# MCU.net
KiCad netlist of a schematic drawn in Altium Designer
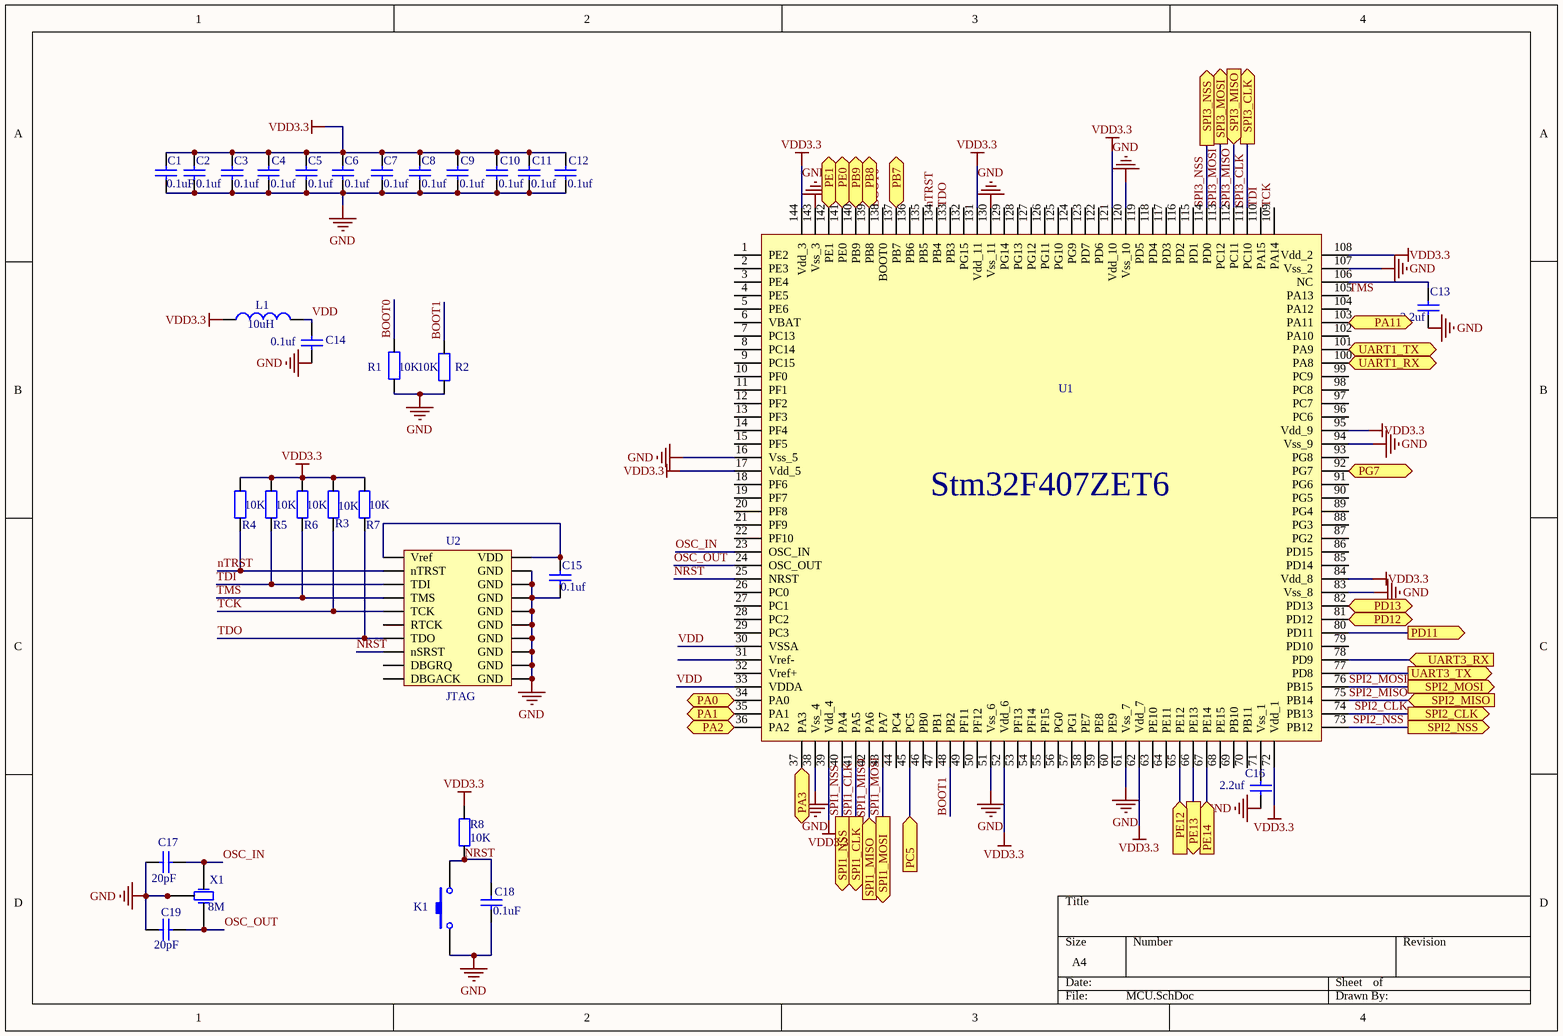
[diagram p0: MCU.SchDoc]

(export (version "E")
  (design (tool "Eeschema 10.0.6"))
  (components
    (comp (ref "C1")
      (value "0.1uF")
      (footprint "0603")
      (fields (field (name "Comment") "Capacitor-0805"))
      (libsource (lib "集成库—大岐") (part "Capacitor-0805"))
    )
    (comp (ref "C2")
      (value "0.1uf")
      (footprint "0603")
      (fields (field (name "Comment") "Capacitor-0805"))
      (libsource (lib "集成库—大岐") (part "Capacitor-0805"))
    )
    (comp (ref "C3")
      (value "0.1uf")
      (footprint "0603")
      (fields (field (name "Comment") "Capacitor-0805"))
      (libsource (lib "集成库—大岐") (part "Capacitor-0805"))
    )
    (comp (ref "C4")
      (value "0.1uf")
      (footprint "0603")
      (fields (field (name "Comment") "Capacitor-0805"))
      (libsource (lib "集成库—大岐") (part "Capacitor-0805"))
    )
    (comp (ref "C5")
      (value "0.1uf")
      (footprint "0603")
      (fields (field (name "Comment") "Capacitor-0805"))
      (libsource (lib "集成库—大岐") (part "Capacitor-0805"))
    )
    (comp (ref "C6")
      (value "0.1uf")
      (footprint "0603")
      (fields (field (name "Comment") "Capacitor-0805"))
      (libsource (lib "集成库—大岐") (part "Capacitor-0805"))
    )
    (comp (ref "C7")
      (value "0.1uf")
      (footprint "0603")
      (fields (field (name "Comment") "Capacitor-0805"))
      (libsource (lib "集成库—大岐") (part "Capacitor-0805"))
    )
    (comp (ref "C8")
      (value "0.1uf")
      (footprint "0603")
      (fields (field (name "Comment") "Capacitor-0805"))
      (libsource (lib "集成库—大岐") (part "Capacitor-0805"))
    )
    (comp (ref "C9")
      (value "0.1uf")
      (footprint "0603")
      (fields (field (name "Comment") "Capacitor-0805"))
      (libsource (lib "集成库—大岐") (part "Capacitor-0805"))
    )
    (comp (ref "C10")
      (value "0.1uf")
      (footprint "0603")
      (fields (field (name "Comment") "Capacitor-0805"))
      (libsource (lib "集成库—大岐") (part "Capacitor-0805"))
    )
    (comp (ref "C11")
      (value "0.1uf")
      (footprint "0603")
      (fields (field (name "Comment") "Capacitor-0805"))
      (libsource (lib "集成库—大岐") (part "Capacitor-0805"))
    )
    (comp (ref "C12")
      (value "0.1uf")
      (footprint "0603")
      (fields (field (name "Comment") "Capacitor-0805"))
      (libsource (lib "集成库—大岐") (part "Capacitor-0805"))
    )
    (comp (ref "C13")
      (value "2.2uf")
      (footprint "0603")
      (fields (field (name "Comment") "Capacitor-0603"))
      (libsource (lib "原理图库") (part "Capacitor-0603"))
    )
    (comp (ref "C14")
      (value "0.1uf")
      (footprint "0603")
      (fields (field (name "Comment") "Capacitor-0805"))
      (libsource (lib "集成库—大岐") (part "Capacitor-0805"))
    )
    (comp (ref "C15")
      (value "0.1uf")
      (footprint "0603")
      (fields (field (name "Comment") "Capacitor-0805"))
      (libsource (lib "集成库—大岐") (part "Capacitor-0805"))
    )
    (comp (ref "C16")
      (value "2.2uf")
      (footprint "0603")
      (fields (field (name "Comment") "Capacitor-0603"))
      (libsource (lib "原理图库") (part "Capacitor-0603"))
    )
    (comp (ref "C17")
      (value "20pF")
      (footprint "0603")
      (fields (field (name "Comment") "Capacitor-0805"))
      (libsource (lib "原理图库") (part "Capacitor-0805"))
    )
    (comp (ref "C18")
      (value "0.1uF")
      (footprint "0603")
      (fields (field (name "Comment") "Capacitor-0805"))
      (libsource (lib "原理图库") (part "Capacitor-0805"))
    )
    (comp (ref "C19")
      (value "20pF")
      (footprint "0603")
      (fields (field (name "Comment") "Capacitor-0805"))
      (libsource (lib "原理图库") (part "Capacitor-0805"))
    )
    (comp (ref "K1") (value "按键") (footprint "贴片按键") (libsource (lib "原理图库") (part "按键")))
    (comp (ref "L1")
      (value "10uH")
      (footprint "0805")
      (fields (field (name "Comment") "Inductor"))
      (libsource (lib "集成库—大岐") (part "Inductor"))
    )
    (comp (ref "R1")
      (value "10K")
      (footprint "0603")
      (fields (field (name "Comment") "Resistor-0805"))
      (libsource (lib "集成库—大岐") (part "Resistor-0805"))
    )
    (comp (ref "R2")
      (value "10K")
      (footprint "0603")
      (fields (field (name "Comment") "Resistor-0805"))
      (libsource (lib "集成库—大岐") (part "Resistor-0805"))
    )
    (comp (ref "R3")
      (value "10K")
      (footprint "0603")
      (fields (field (name "Comment") "Resistor-0805"))
      (libsource (lib "原理图库") (part "Resistor-0805"))
    )
    (comp (ref "R4")
      (value "10K")
      (footprint "0603")
      (fields (field (name "Comment") "Resistor-0805"))
      (libsource (lib "原理图库") (part "Resistor-0805"))
    )
    (comp (ref "R5")
      (value "10K")
      (footprint "0603")
      (fields (field (name "Comment") "Resistor-0805"))
      (libsource (lib "原理图库") (part "Resistor-0805"))
    )
    (comp (ref "R6")
      (value "10K")
      (footprint "0603")
      (fields (field (name "Comment") "Resistor-0805"))
      (libsource (lib "原理图库") (part "Resistor-0805"))
    )
    (comp (ref "R7")
      (value "10K")
      (footprint "0603")
      (fields (field (name "Comment") "Resistor-0805"))
      (libsource (lib "原理图库") (part "Resistor-0805"))
    )
    (comp (ref "R8")
      (value "10K")
      (footprint "0603")
      (fields (field (name "Comment") "Resistor-0805"))
      (libsource (lib "原理图库") (part "Resistor-0805"))
    )
    (comp (ref "U1")
      (value "STM32F407ZET6")
      (footprint "Stm32f407ZET6 - duplicate")
      (libsource (lib "原理图库") (part "STM32F407ZET6"))
    )
    (comp (ref "U2") (value "JTAG") (footprint "JTAG-20") (libsource (lib "原理图库") (part "JTAG")))
    (comp (ref "X1")
      (value "8M")
      (footprint "3225无源晶振")
      (fields (field (name "Comment") "3225无源晶振"))
      (libsource (lib "原理图库") (part "3225无源晶振"))
    )
  )
  (nets
    (net (code "1") (name "/BOOT0") (class "Default")
      (node (ref "R1") (pin "2") (pinfunction "2_2") (pintype "passive"))
      (node (ref "U1") (pin "138") (pinfunction "BOOT0_138") (pintype "passive"))
    )
    (net (code "2") (name "/BOOT1") (class "Default")
      (node (ref "R2") (pin "2") (pinfunction "2_2") (pintype "passive"))
      (node (ref "U1") (pin "48") (pinfunction "PB2_48") (pintype "passive"))
    )
    (net (code "3") (name "/NRST") (class "Default")
      (node (ref "C18") (pin "2") (pinfunction "2_2") (pintype "passive"))
      (node (ref "K1") (pin "2") (pinfunction "2_2") (pintype "passive"))
      (node (ref "R8") (pin "1") (pinfunction "1_1") (pintype "passive"))
      (node (ref "U1") (pin "25") (pinfunction "NRST_25") (pintype "passive"))
      (node (ref "U2") (pin "15") (pinfunction "nSRST_15") (pintype "passive"))
    )
    (net (code "4") (name "/OSC_IN") (class "Default")
      (node (ref "C17") (pin "2") (pinfunction "2_2") (pintype "passive"))
      (node (ref "U1") (pin "23") (pinfunction "OSC_IN_23") (pintype "passive"))
      (node (ref "X1") (pin "1") (pinfunction "OSC1_1") (pintype "passive"))
    )
    (net (code "5") (name "/OSC_OUT") (class "Default")
      (node (ref "C19") (pin "2") (pinfunction "2_2") (pintype "passive"))
      (node (ref "U1") (pin "24") (pinfunction "OSC_OUT_24") (pintype "passive"))
      (node (ref "X1") (pin "3") (pinfunction "OSC2_3") (pintype "passive"))
    )
    (net (code "6") (name "/PA0") (class "Default")
      (node (ref "U1") (pin "34") (pinfunction "PA0_34") (pintype "passive"))
    )
    (net (code "7") (name "/PA1") (class "Default")
      (node (ref "U1") (pin "35") (pinfunction "PA1_35") (pintype "passive"))
    )
    (net (code "8") (name "/PA2") (class "Default")
      (node (ref "U1") (pin "36") (pinfunction "PA2_36") (pintype "passive"))
    )
    (net (code "9") (name "/PA3") (class "Default")
      (node (ref "U1") (pin "37") (pinfunction "PA3_37") (pintype "passive"))
    )
    (net (code "10") (name "/PA11") (class "Default")
      (node (ref "U1") (pin "103") (pinfunction "PA11_103") (pintype "passive"))
    )
    (net (code "11") (name "/PB7") (class "Default")
      (node (ref "U1") (pin "137") (pinfunction "PB7_137") (pintype "passive"))
    )
    (net (code "12") (name "/PB8") (class "Default")
      (node (ref "U1") (pin "139") (pinfunction "PB8_139") (pintype "passive"))
    )
    (net (code "13") (name "/PB9") (class "Default")
      (node (ref "U1") (pin "140") (pinfunction "PB9_140") (pintype "passive"))
    )
    (net (code "14") (name "/PC5") (class "Default")
      (node (ref "U1") (pin "45") (pinfunction "PC5_45") (pintype "passive"))
    )
    (net (code "15") (name "/PD11") (class "Default")
      (node (ref "U1") (pin "80") (pinfunction "PD11_80") (pintype "passive"))
    )
    (net (code "16") (name "/PD12") (class "Default")
      (node (ref "U1") (pin "81") (pinfunction "PD12_81") (pintype "passive"))
    )
    (net (code "17") (name "/PD13") (class "Default")
      (node (ref "U1") (pin "82") (pinfunction "PD13_82") (pintype "passive"))
    )
    (net (code "18") (name "/PE0") (class "Default")
      (node (ref "U1") (pin "141") (pinfunction "PE0_141") (pintype "passive"))
    )
    (net (code "19") (name "/PE1") (class "Default")
      (node (ref "U1") (pin "142") (pinfunction "PE1_142") (pintype "passive"))
    )
    (net (code "20") (name "/PE12") (class "Default")
      (node (ref "U1") (pin "65") (pinfunction "PE12_65") (pintype "passive"))
    )
    (net (code "21") (name "/PE13") (class "Default")
      (node (ref "U1") (pin "66") (pinfunction "PE13_66") (pintype "passive"))
    )
    (net (code "22") (name "/PE14") (class "Default")
      (node (ref "U1") (pin "67") (pinfunction "PE14_67") (pintype "passive"))
    )
    (net (code "23") (name "/PG7") (class "Default")
      (node (ref "U1") (pin "92") (pinfunction "PG7_92") (pintype "passive"))
    )
    (net (code "24") (name "/SPI1_CLK") (class "Default")
      (node (ref "U1") (pin "41") (pinfunction "PA5_41") (pintype "passive"))
    )
    (net (code "25") (name "/SPI1_MISO") (class "Default")
      (node (ref "U1") (pin "42") (pinfunction "PA6_42") (pintype "passive"))
    )
    (net (code "26") (name "/SPI1_MOSI") (class "Default")
      (node (ref "U1") (pin "43") (pinfunction "PA7_43") (pintype "passive"))
    )
    (net (code "27") (name "/SPI1_NSS") (class "Default")
      (node (ref "U1") (pin "40") (pinfunction "PA4_40") (pintype "passive"))
    )
    (net (code "28") (name "/SPI2_CLK") (class "Default")
      (node (ref "U1") (pin "74") (pinfunction "PB13_74") (pintype "passive"))
    )
    (net (code "29") (name "/SPI2_MISO") (class "Default")
      (node (ref "U1") (pin "75") (pinfunction "PB14_75") (pintype "passive"))
    )
    (net (code "30") (name "/SPI2_MOSI") (class "Default")
      (node (ref "U1") (pin "76") (pinfunction "PB15_76") (pintype "passive"))
    )
    (net (code "31") (name "/SPI2_NSS") (class "Default")
      (node (ref "U1") (pin "73") (pinfunction "PB12_73") (pintype "passive"))
    )
    (net (code "32") (name "/SPI3_CLK") (class "Default")
      (node (ref "U1") (pin "111") (pinfunction "PC10_111") (pintype "passive"))
    )
    (net (code "33") (name "/SPI3_MISO") (class "Default")
      (node (ref "U1") (pin "112") (pinfunction "PC11_112") (pintype "passive"))
    )
    (net (code "34") (name "/SPI3_MOSI") (class "Default")
      (node (ref "U1") (pin "113") (pinfunction "PC12_113") (pintype "passive"))
    )
    (net (code "35") (name "/SPI3_NSS") (class "Default")
      (node (ref "U1") (pin "114") (pinfunction "PD0_114") (pintype "passive"))
    )
    (net (code "36") (name "/TCK") (class "Default")
      (node (ref "R3") (pin "1") (pinfunction "1_1") (pintype "passive"))
      (node (ref "U1") (pin "109") (pinfunction "PA14_109") (pintype "passive"))
      (node (ref "U2") (pin "9") (pinfunction "TCK_9") (pintype "passive"))
    )
    (net (code "37") (name "/TDI") (class "Default")
      (node (ref "R5") (pin "1") (pinfunction "1_1") (pintype "passive"))
      (node (ref "U1") (pin "110") (pinfunction "PA15_110") (pintype "passive"))
      (node (ref "U2") (pin "5") (pinfunction "TDI_5") (pintype "passive"))
    )
    (net (code "38") (name "/TDO") (class "Default")
      (node (ref "R7") (pin "1") (pinfunction "1_1") (pintype "passive"))
      (node (ref "U1") (pin "133") (pinfunction "PB3_133") (pintype "passive"))
      (node (ref "U2") (pin "13") (pinfunction "TDO_13") (pintype "passive"))
    )
    (net (code "39") (name "/TMS") (class "Default")
      (node (ref "R6") (pin "1") (pinfunction "1_1") (pintype "passive"))
      (node (ref "U1") (pin "105") (pinfunction "PA13_105") (pintype "passive"))
      (node (ref "U2") (pin "7") (pinfunction "TMS_7") (pintype "passive"))
    )
    (net (code "40") (name "/UART1_RX") (class "Default")
      (node (ref "U1") (pin "100") (pinfunction "PA8_100") (pintype "passive"))
    )
    (net (code "41") (name "/UART1_TX") (class "Default")
      (node (ref "U1") (pin "101") (pinfunction "PA9_101") (pintype "passive"))
    )
    (net (code "42") (name "/UART3_RX") (class "Default")
      (node (ref "U1") (pin "78") (pinfunction "PD9_78") (pintype "passive"))
    )
    (net (code "43") (name "/UART3_TX") (class "Default")
      (node (ref "U1") (pin "77") (pinfunction "PD8_77") (pintype "passive"))
    )
    (net (code "44") (name "/VDD") (class "Default")
      (node (ref "C14") (pin "2") (pinfunction "2_2") (pintype "passive"))
      (node (ref "L1") (pin "2") (pinfunction "2_2") (pintype "passive"))
      (node (ref "U1") (pin "30") (pinfunction "VSSA_30") (pintype "passive"))
      (node (ref "U1") (pin "33") (pinfunction "VDDA_33") (pintype "passive"))
    )
    (net (code "45") (name "/nTRST") (class "Default")
      (node (ref "R4") (pin "1") (pinfunction "1_1") (pintype "passive"))
      (node (ref "U1") (pin "134") (pinfunction "PB4_134") (pintype "passive"))
      (node (ref "U2") (pin "3") (pinfunction "nTRST_3") (pintype "passive"))
    )
    (net (code "46") (name "GND") (class "Default")
      (node (ref "C1") (pin "1") (pinfunction "1_1") (pintype "passive"))
      (node (ref "C10") (pin "1") (pinfunction "1_1") (pintype "passive"))
      (node (ref "C11") (pin "1") (pinfunction "1_1") (pintype "passive"))
      (node (ref "C12") (pin "1") (pinfunction "1_1") (pintype "passive"))
      (node (ref "C13") (pin "1") (pinfunction "1_1") (pintype "passive"))
      (node (ref "C14") (pin "1") (pinfunction "1_1") (pintype "passive"))
      (node (ref "C15") (pin "1") (pinfunction "1_1") (pintype "passive"))
      (node (ref "C16") (pin "1") (pinfunction "1_1") (pintype "passive"))
      (node (ref "C17") (pin "1") (pinfunction "1_1") (pintype "passive"))
      (node (ref "C18") (pin "1") (pinfunction "1_1") (pintype "passive"))
      (node (ref "C19") (pin "1") (pinfunction "1_1") (pintype "passive"))
      (node (ref "C2") (pin "1") (pinfunction "1_1") (pintype "passive"))
      (node (ref "C3") (pin "1") (pinfunction "1_1") (pintype "passive"))
      (node (ref "C4") (pin "1") (pinfunction "1_1") (pintype "passive"))
      (node (ref "C5") (pin "1") (pinfunction "1_1") (pintype "passive"))
      (node (ref "C6") (pin "1") (pinfunction "1_1") (pintype "passive"))
      (node (ref "C7") (pin "1") (pinfunction "1_1") (pintype "passive"))
      (node (ref "C8") (pin "1") (pinfunction "1_1") (pintype "passive"))
      (node (ref "C9") (pin "1") (pinfunction "1_1") (pintype "passive"))
      (node (ref "K1") (pin "1") (pinfunction "1_1") (pintype "passive"))
      (node (ref "R1") (pin "1") (pinfunction "1_1") (pintype "passive"))
      (node (ref "R2") (pin "1") (pinfunction "1_1") (pintype "passive"))
      (node (ref "U1") (pin "107") (pinfunction "Vss_2_107") (pintype "passive"))
      (node (ref "U1") (pin "120") (pinfunction "Vss_10_120") (pintype "passive"))
      (node (ref "U1") (pin "130") (pinfunction "Vss_11_130") (pintype "passive"))
      (node (ref "U1") (pin "143") (pinfunction "Vss_3_143") (pintype "passive"))
      (node (ref "U1") (pin "16") (pinfunction "Vss_5_16") (pintype "passive"))
      (node (ref "U1") (pin "38") (pinfunction "Vss_4_38") (pintype "passive"))
      (node (ref "U1") (pin "51") (pinfunction "Vss_6_51") (pintype "passive"))
      (node (ref "U1") (pin "61") (pinfunction "Vss_7_61") (pintype "passive"))
      (node (ref "U1") (pin "83") (pinfunction "Vss_8_83") (pintype "passive"))
      (node (ref "U1") (pin "94") (pinfunction "Vss_9_94") (pintype "passive"))
      (node (ref "U2") (pin "10") (pinfunction "GND_10") (pintype "passive"))
      (node (ref "U2") (pin "12") (pinfunction "GND_12") (pintype "passive"))
      (node (ref "U2") (pin "14") (pinfunction "GND_14") (pintype "passive"))
      (node (ref "U2") (pin "16") (pinfunction "GND_16") (pintype "passive"))
      (node (ref "U2") (pin "18") (pinfunction "GND_18") (pintype "passive"))
      (node (ref "U2") (pin "20") (pinfunction "GND_20") (pintype "passive"))
      (node (ref "U2") (pin "4") (pinfunction "GND_4") (pintype "passive"))
      (node (ref "U2") (pin "6") (pinfunction "GND_6") (pintype "passive"))
      (node (ref "U2") (pin "8") (pinfunction "GND_8") (pintype "passive"))
      (node (ref "X1") (pin "2") (pinfunction "GND_2") (pintype "passive"))
      (node (ref "X1") (pin "4") (pinfunction "GND_4") (pintype "passive"))
    )
    (net (code "47") (name "Net-(U1-NC)") (class "Default")
      (node (ref "C13") (pin "2") (pinfunction "2_2") (pintype "passive"))
      (node (ref "U1") (pin "106") (pinfunction "NC_106") (pintype "passive"))
    )
    (net (code "48") (name "Net-(U1-Vss_1)") (class "Default")
      (node (ref "C16") (pin "2") (pinfunction "2_2") (pintype "passive"))
      (node (ref "U1") (pin "71") (pinfunction "Vss_1_71") (pintype "passive"))
    )
    (net (code "49") (name "Net-(U2-VDD)") (class "Default")
      (node (ref "C15") (pin "2") (pinfunction "2_2") (pintype "passive"))
      (node (ref "U2") (pin "1") (pinfunction "Vref_1") (pintype "passive"))
      (node (ref "U2") (pin "2") (pinfunction "VDD_2") (pintype "passive"))
    )
    (net (code "50") (name "VDD3.3") (class "Default")
      (node (ref "C1") (pin "2") (pinfunction "2_2") (pintype "passive"))
      (node (ref "C10") (pin "2") (pinfunction "2_2") (pintype "passive"))
      (node (ref "C11") (pin "2") (pinfunction "2_2") (pintype "passive"))
      (node (ref "C12") (pin "2") (pinfunction "2_2") (pintype "passive"))
      (node (ref "C2") (pin "2") (pinfunction "2_2") (pintype "passive"))
      (node (ref "C3") (pin "2") (pinfunction "2_2") (pintype "passive"))
      (node (ref "C4") (pin "2") (pinfunction "2_2") (pintype "passive"))
      (node (ref "C5") (pin "2") (pinfunction "2_2") (pintype "passive"))
      (node (ref "C6") (pin "2") (pinfunction "2_2") (pintype "passive"))
      (node (ref "C7") (pin "2") (pinfunction "2_2") (pintype "passive"))
      (node (ref "C8") (pin "2") (pinfunction "2_2") (pintype "passive"))
      (node (ref "C9") (pin "2") (pinfunction "2_2") (pintype "passive"))
      (node (ref "L1") (pin "1") (pinfunction "1_1") (pintype "passive"))
      (node (ref "R3") (pin "2") (pinfunction "2_2") (pintype "passive"))
      (node (ref "R4") (pin "2") (pinfunction "2_2") (pintype "passive"))
      (node (ref "R5") (pin "2") (pinfunction "2_2") (pintype "passive"))
      (node (ref "R6") (pin "2") (pinfunction "2_2") (pintype "passive"))
      (node (ref "R7") (pin "2") (pinfunction "2_2") (pintype "passive"))
      (node (ref "R8") (pin "2") (pinfunction "2_2") (pintype "passive"))
      (node (ref "U1") (pin "108") (pinfunction "Vdd_2_108") (pintype "passive"))
      (node (ref "U1") (pin "121") (pinfunction "Vdd_10_121") (pintype "passive"))
      (node (ref "U1") (pin "131") (pinfunction "Vdd_11_131") (pintype "passive"))
      (node (ref "U1") (pin "144") (pinfunction "Vdd_3_144") (pintype "passive"))
      (node (ref "U1") (pin "17") (pinfunction "Vdd_5_17") (pintype "passive"))
      (node (ref "U1") (pin "39") (pinfunction "Vdd_4_39") (pintype "passive"))
      (node (ref "U1") (pin "52") (pinfunction "Vdd_6_52") (pintype "passive"))
      (node (ref "U1") (pin "62") (pinfunction "Vdd_7_62") (pintype "passive"))
      (node (ref "U1") (pin "72") (pinfunction "Vdd_1_72") (pintype "passive"))
      (node (ref "U1") (pin "84") (pinfunction "Vdd_8_84") (pintype "passive"))
      (node (ref "U1") (pin "95") (pinfunction "Vdd_9_95") (pintype "passive"))
    )
    (net (code "51") (name "unconnected-(U1-PA10-Pad102)") (class "Default")
      (node (ref "U1") (pin "102") (pinfunction "PA10_102") (pintype "passive"))
    )
    (net (code "52") (name "unconnected-(U1-PA12-Pad104)") (class "Default")
      (node (ref "U1") (pin "104") (pinfunction "PA12_104") (pintype "passive"))
    )
    (net (code "53") (name "unconnected-(U1-PB0-Pad46)") (class "Default")
      (node (ref "U1") (pin "46") (pinfunction "PB0_46") (pintype "passive"))
    )
    (net (code "54") (name "unconnected-(U1-PB1-Pad47)") (class "Default")
      (node (ref "U1") (pin "47") (pinfunction "PB1_47") (pintype "passive"))
    )
    (net (code "55") (name "unconnected-(U1-PB5-Pad135)") (class "Default")
      (node (ref "U1") (pin "135") (pinfunction "PB5_135") (pintype "passive"))
    )
    (net (code "56") (name "unconnected-(U1-PB6-Pad136)") (class "Default")
      (node (ref "U1") (pin "136") (pinfunction "PB6_136") (pintype "passive"))
    )
    (net (code "57") (name "unconnected-(U1-PB10-Pad69)") (class "Default")
      (node (ref "U1") (pin "69") (pinfunction "PB10_69") (pintype "passive"))
    )
    (net (code "58") (name "unconnected-(U1-PB11-Pad70)") (class "Default")
      (node (ref "U1") (pin "70") (pinfunction "PB11_70") (pintype "passive"))
    )
    (net (code "59") (name "unconnected-(U1-PC0-Pad26)") (class "Default")
      (node (ref "U1") (pin "26") (pinfunction "PC0_26") (pintype "passive"))
    )
    (net (code "60") (name "unconnected-(U1-PC1-Pad27)") (class "Default")
      (node (ref "U1") (pin "27") (pinfunction "PC1_27") (pintype "passive"))
    )
    (net (code "61") (name "unconnected-(U1-PC2-Pad28)") (class "Default")
      (node (ref "U1") (pin "28") (pinfunction "PC2_28") (pintype "passive"))
    )
    (net (code "62") (name "unconnected-(U1-PC3-Pad29)") (class "Default")
      (node (ref "U1") (pin "29") (pinfunction "PC3_29") (pintype "passive"))
    )
    (net (code "63") (name "unconnected-(U1-PC4-Pad44)") (class "Default")
      (node (ref "U1") (pin "44") (pinfunction "PC4_44") (pintype "passive"))
    )
    (net (code "64") (name "unconnected-(U1-PC6-Pad96)") (class "Default")
      (node (ref "U1") (pin "96") (pinfunction "PC6_96") (pintype "passive"))
    )
    (net (code "65") (name "unconnected-(U1-PC7-Pad97)") (class "Default")
      (node (ref "U1") (pin "97") (pinfunction "PC7_97") (pintype "passive"))
    )
    (net (code "66") (name "unconnected-(U1-PC8-Pad98)") (class "Default")
      (node (ref "U1") (pin "98") (pinfunction "PC8_98") (pintype "passive"))
    )
    (net (code "67") (name "unconnected-(U1-PC9-Pad99)") (class "Default")
      (node (ref "U1") (pin "99") (pinfunction "PC9_99") (pintype "passive"))
    )
    (net (code "68") (name "unconnected-(U1-PC13-Pad7)") (class "Default")
      (node (ref "U1") (pin "7") (pinfunction "PC13_7") (pintype "passive"))
    )
    (net (code "69") (name "unconnected-(U1-PC14-Pad8)") (class "Default")
      (node (ref "U1") (pin "8") (pinfunction "PC14_8") (pintype "passive"))
    )
    (net (code "70") (name "unconnected-(U1-PC15-Pad9)") (class "Default")
      (node (ref "U1") (pin "9") (pinfunction "PC15_9") (pintype "passive"))
    )
    (net (code "71") (name "unconnected-(U1-PD1-Pad115)") (class "Default")
      (node (ref "U1") (pin "115") (pinfunction "PD1_115") (pintype "passive"))
    )
    (net (code "72") (name "unconnected-(U1-PD2-Pad116)") (class "Default")
      (node (ref "U1") (pin "116") (pinfunction "PD2_116") (pintype "passive"))
    )
    (net (code "73") (name "unconnected-(U1-PD3-Pad117)") (class "Default")
      (node (ref "U1") (pin "117") (pinfunction "PD3_117") (pintype "passive"))
    )
    (net (code "74") (name "unconnected-(U1-PD4-Pad118)") (class "Default")
      (node (ref "U1") (pin "118") (pinfunction "PD4_118") (pintype "passive"))
    )
    (net (code "75") (name "unconnected-(U1-PD5-Pad119)") (class "Default")
      (node (ref "U1") (pin "119") (pinfunction "PD5_119") (pintype "passive"))
    )
    (net (code "76") (name "unconnected-(U1-PD6-Pad122)") (class "Default")
      (node (ref "U1") (pin "122") (pinfunction "PD6_122") (pintype "passive"))
    )
    (net (code "77") (name "unconnected-(U1-PD7-Pad123)") (class "Default")
      (node (ref "U1") (pin "123") (pinfunction "PD7_123") (pintype "passive"))
    )
    (net (code "78") (name "unconnected-(U1-PD10-Pad79)") (class "Default")
      (node (ref "U1") (pin "79") (pinfunction "PD10_79") (pintype "passive"))
    )
    (net (code "79") (name "unconnected-(U1-PD14-Pad85)") (class "Default")
      (node (ref "U1") (pin "85") (pinfunction "PD14_85") (pintype "passive"))
    )
    (net (code "80") (name "unconnected-(U1-PD15-Pad86)") (class "Default")
      (node (ref "U1") (pin "86") (pinfunction "PD15_86") (pintype "passive"))
    )
    (net (code "81") (name "unconnected-(U1-PE2-Pad1)") (class "Default")
      (node (ref "U1") (pin "1") (pinfunction "PE2_1") (pintype "passive"))
    )
    (net (code "82") (name "unconnected-(U1-PE3-Pad2)") (class "Default")
      (node (ref "U1") (pin "2") (pinfunction "PE3_2") (pintype "passive"))
    )
    (net (code "83") (name "unconnected-(U1-PE4-Pad3)") (class "Default")
      (node (ref "U1") (pin "3") (pinfunction "PE4_3") (pintype "passive"))
    )
    (net (code "84") (name "unconnected-(U1-PE5-Pad4)") (class "Default")
      (node (ref "U1") (pin "4") (pinfunction "PE5_4") (pintype "passive"))
    )
    (net (code "85") (name "unconnected-(U1-PE6-Pad5)") (class "Default")
      (node (ref "U1") (pin "5") (pinfunction "PE6_5") (pintype "passive"))
    )
    (net (code "86") (name "unconnected-(U1-PE7-Pad58)") (class "Default")
      (node (ref "U1") (pin "58") (pinfunction "PE7_58") (pintype "passive"))
    )
    (net (code "87") (name "unconnected-(U1-PE8-Pad59)") (class "Default")
      (node (ref "U1") (pin "59") (pinfunction "PE8_59") (pintype "passive"))
    )
    (net (code "88") (name "unconnected-(U1-PE9-Pad60)") (class "Default")
      (node (ref "U1") (pin "60") (pinfunction "PE9_60") (pintype "passive"))
    )
    (net (code "89") (name "unconnected-(U1-PE10-Pad63)") (class "Default")
      (node (ref "U1") (pin "63") (pinfunction "PE10_63") (pintype "passive"))
    )
    (net (code "90") (name "unconnected-(U1-PE11-Pad64)") (class "Default")
      (node (ref "U1") (pin "64") (pinfunction "PE11_64") (pintype "passive"))
    )
    (net (code "91") (name "unconnected-(U1-PE15-Pad68)") (class "Default")
      (node (ref "U1") (pin "68") (pinfunction "PE15_68") (pintype "passive"))
    )
    (net (code "92") (name "unconnected-(U1-PF0-Pad10)") (class "Default")
      (node (ref "U1") (pin "10") (pinfunction "PF0_10") (pintype "passive"))
    )
    (net (code "93") (name "unconnected-(U1-PF1-Pad11)") (class "Default")
      (node (ref "U1") (pin "11") (pinfunction "PF1_11") (pintype "passive"))
    )
    (net (code "94") (name "unconnected-(U1-PF2-Pad12)") (class "Default")
      (node (ref "U1") (pin "12") (pinfunction "PF2_12") (pintype "passive"))
    )
    (net (code "95") (name "unconnected-(U1-PF3-Pad13)") (class "Default")
      (node (ref "U1") (pin "13") (pinfunction "PF3_13") (pintype "passive"))
    )
    (net (code "96") (name "unconnected-(U1-PF4-Pad14)") (class "Default")
      (node (ref "U1") (pin "14") (pinfunction "PF4_14") (pintype "passive"))
    )
    (net (code "97") (name "unconnected-(U1-PF5-Pad15)") (class "Default")
      (node (ref "U1") (pin "15") (pinfunction "PF5_15") (pintype "passive"))
    )
    (net (code "98") (name "unconnected-(U1-PF6-Pad18)") (class "Default")
      (node (ref "U1") (pin "18") (pinfunction "PF6_18") (pintype "passive"))
    )
    (net (code "99") (name "unconnected-(U1-PF7-Pad19)") (class "Default")
      (node (ref "U1") (pin "19") (pinfunction "PF7_19") (pintype "passive"))
    )
    (net (code "100") (name "unconnected-(U1-PF8-Pad20)") (class "Default")
      (node (ref "U1") (pin "20") (pinfunction "PF8_20") (pintype "passive"))
    )
    (net (code "101") (name "unconnected-(U1-PF9-Pad21)") (class "Default")
      (node (ref "U1") (pin "21") (pinfunction "PF9_21") (pintype "passive"))
    )
    (net (code "102") (name "unconnected-(U1-PF10-Pad22)") (class "Default")
      (node (ref "U1") (pin "22") (pinfunction "PF10_22") (pintype "passive"))
    )
    (net (code "103") (name "unconnected-(U1-PF11-Pad49)") (class "Default")
      (node (ref "U1") (pin "49") (pinfunction "PF11_49") (pintype "passive"))
    )
    (net (code "104") (name "unconnected-(U1-PF12-Pad50)") (class "Default")
      (node (ref "U1") (pin "50") (pinfunction "PF12_50") (pintype "passive"))
    )
    (net (code "105") (name "unconnected-(U1-PF13-Pad53)") (class "Default")
      (node (ref "U1") (pin "53") (pinfunction "PF13_53") (pintype "passive"))
    )
    (net (code "106") (name "unconnected-(U1-PF14-Pad54)") (class "Default")
      (node (ref "U1") (pin "54") (pinfunction "PF14_54") (pintype "passive"))
    )
    (net (code "107") (name "unconnected-(U1-PF15-Pad55)") (class "Default")
      (node (ref "U1") (pin "55") (pinfunction "PF15_55") (pintype "passive"))
    )
    (net (code "108") (name "unconnected-(U1-PG0-Pad56)") (class "Default")
      (node (ref "U1") (pin "56") (pinfunction "PG0_56") (pintype "passive"))
    )
    (net (code "109") (name "unconnected-(U1-PG1-Pad57)") (class "Default")
      (node (ref "U1") (pin "57") (pinfunction "PG1_57") (pintype "passive"))
    )
    (net (code "110") (name "unconnected-(U1-PG2-Pad87)") (class "Default")
      (node (ref "U1") (pin "87") (pinfunction "PG2_87") (pintype "passive"))
    )
    (net (code "111") (name "unconnected-(U1-PG3-Pad88)") (class "Default")
      (node (ref "U1") (pin "88") (pinfunction "PG3_88") (pintype "passive"))
    )
    (net (code "112") (name "unconnected-(U1-PG4-Pad89)") (class "Default")
      (node (ref "U1") (pin "89") (pinfunction "PG4_89") (pintype "passive"))
    )
    (net (code "113") (name "unconnected-(U1-PG5-Pad90)") (class "Default")
      (node (ref "U1") (pin "90") (pinfunction "PG5_90") (pintype "passive"))
    )
    (net (code "114") (name "unconnected-(U1-PG6-Pad91)") (class "Default")
      (node (ref "U1") (pin "91") (pinfunction "PG6_91") (pintype "passive"))
    )
    (net (code "115") (name "unconnected-(U1-PG8-Pad93)") (class "Default")
      (node (ref "U1") (pin "93") (pinfunction "PG8_93") (pintype "passive"))
    )
    (net (code "116") (name "unconnected-(U1-PG9-Pad124)") (class "Default")
      (node (ref "U1") (pin "124") (pinfunction "PG9_124") (pintype "passive"))
    )
    (net (code "117") (name "unconnected-(U1-PG10-Pad125)") (class "Default")
      (node (ref "U1") (pin "125") (pinfunction "PG10_125") (pintype "passive"))
    )
    (net (code "118") (name "unconnected-(U1-PG11-Pad126)") (class "Default")
      (node (ref "U1") (pin "126") (pinfunction "PG11_126") (pintype "passive"))
    )
    (net (code "119") (name "unconnected-(U1-PG12-Pad127)") (class "Default")
      (node (ref "U1") (pin "127") (pinfunction "PG12_127") (pintype "passive"))
    )
    (net (code "120") (name "unconnected-(U1-PG13-Pad128)") (class "Default")
      (node (ref "U1") (pin "128") (pinfunction "PG13_128") (pintype "passive"))
    )
    (net (code "121") (name "unconnected-(U1-PG14-Pad129)") (class "Default")
      (node (ref "U1") (pin "129") (pinfunction "PG14_129") (pintype "passive"))
    )
    (net (code "122") (name "unconnected-(U1-PG15-Pad132)") (class "Default")
      (node (ref "U1") (pin "132") (pinfunction "PG15_132") (pintype "passive"))
    )
    (net (code "123") (name "unconnected-(U1-VBAT-Pad6)") (class "Default")
      (node (ref "U1") (pin "6") (pinfunction "VBAT_6") (pintype "passive"))
    )
    (net (code "124") (name "unconnected-(U1-Vref+-Pad32)") (class "Default")
      (node (ref "U1") (pin "32") (pinfunction "Vref+_32") (pintype "passive"))
    )
    (net (code "125") (name "unconnected-(U1-Vref--Pad31)") (class "Default")
      (node (ref "U1") (pin "31") (pinfunction "Vref-_31") (pintype "passive"))
    )
    (net (code "126") (name "unconnected-(U2-DBGACK-Pad19)") (class "Default")
      (node (ref "U2") (pin "19") (pinfunction "DBGACK_19") (pintype "passive"))
    )
    (net (code "127") (name "unconnected-(U2-DBGRQ-Pad17)") (class "Default")
      (node (ref "U2") (pin "17") (pinfunction "DBGRQ_17") (pintype "passive"))
    )
    (net (code "128") (name "unconnected-(U2-RTCK-Pad11)") (class "Default")
      (node (ref "U2") (pin "11") (pinfunction "RTCK_11") (pintype "passive"))
    )
  )
)
